# SDISK2_V0_3.net
KiCad netlist of a schematic drawn in EAGLE
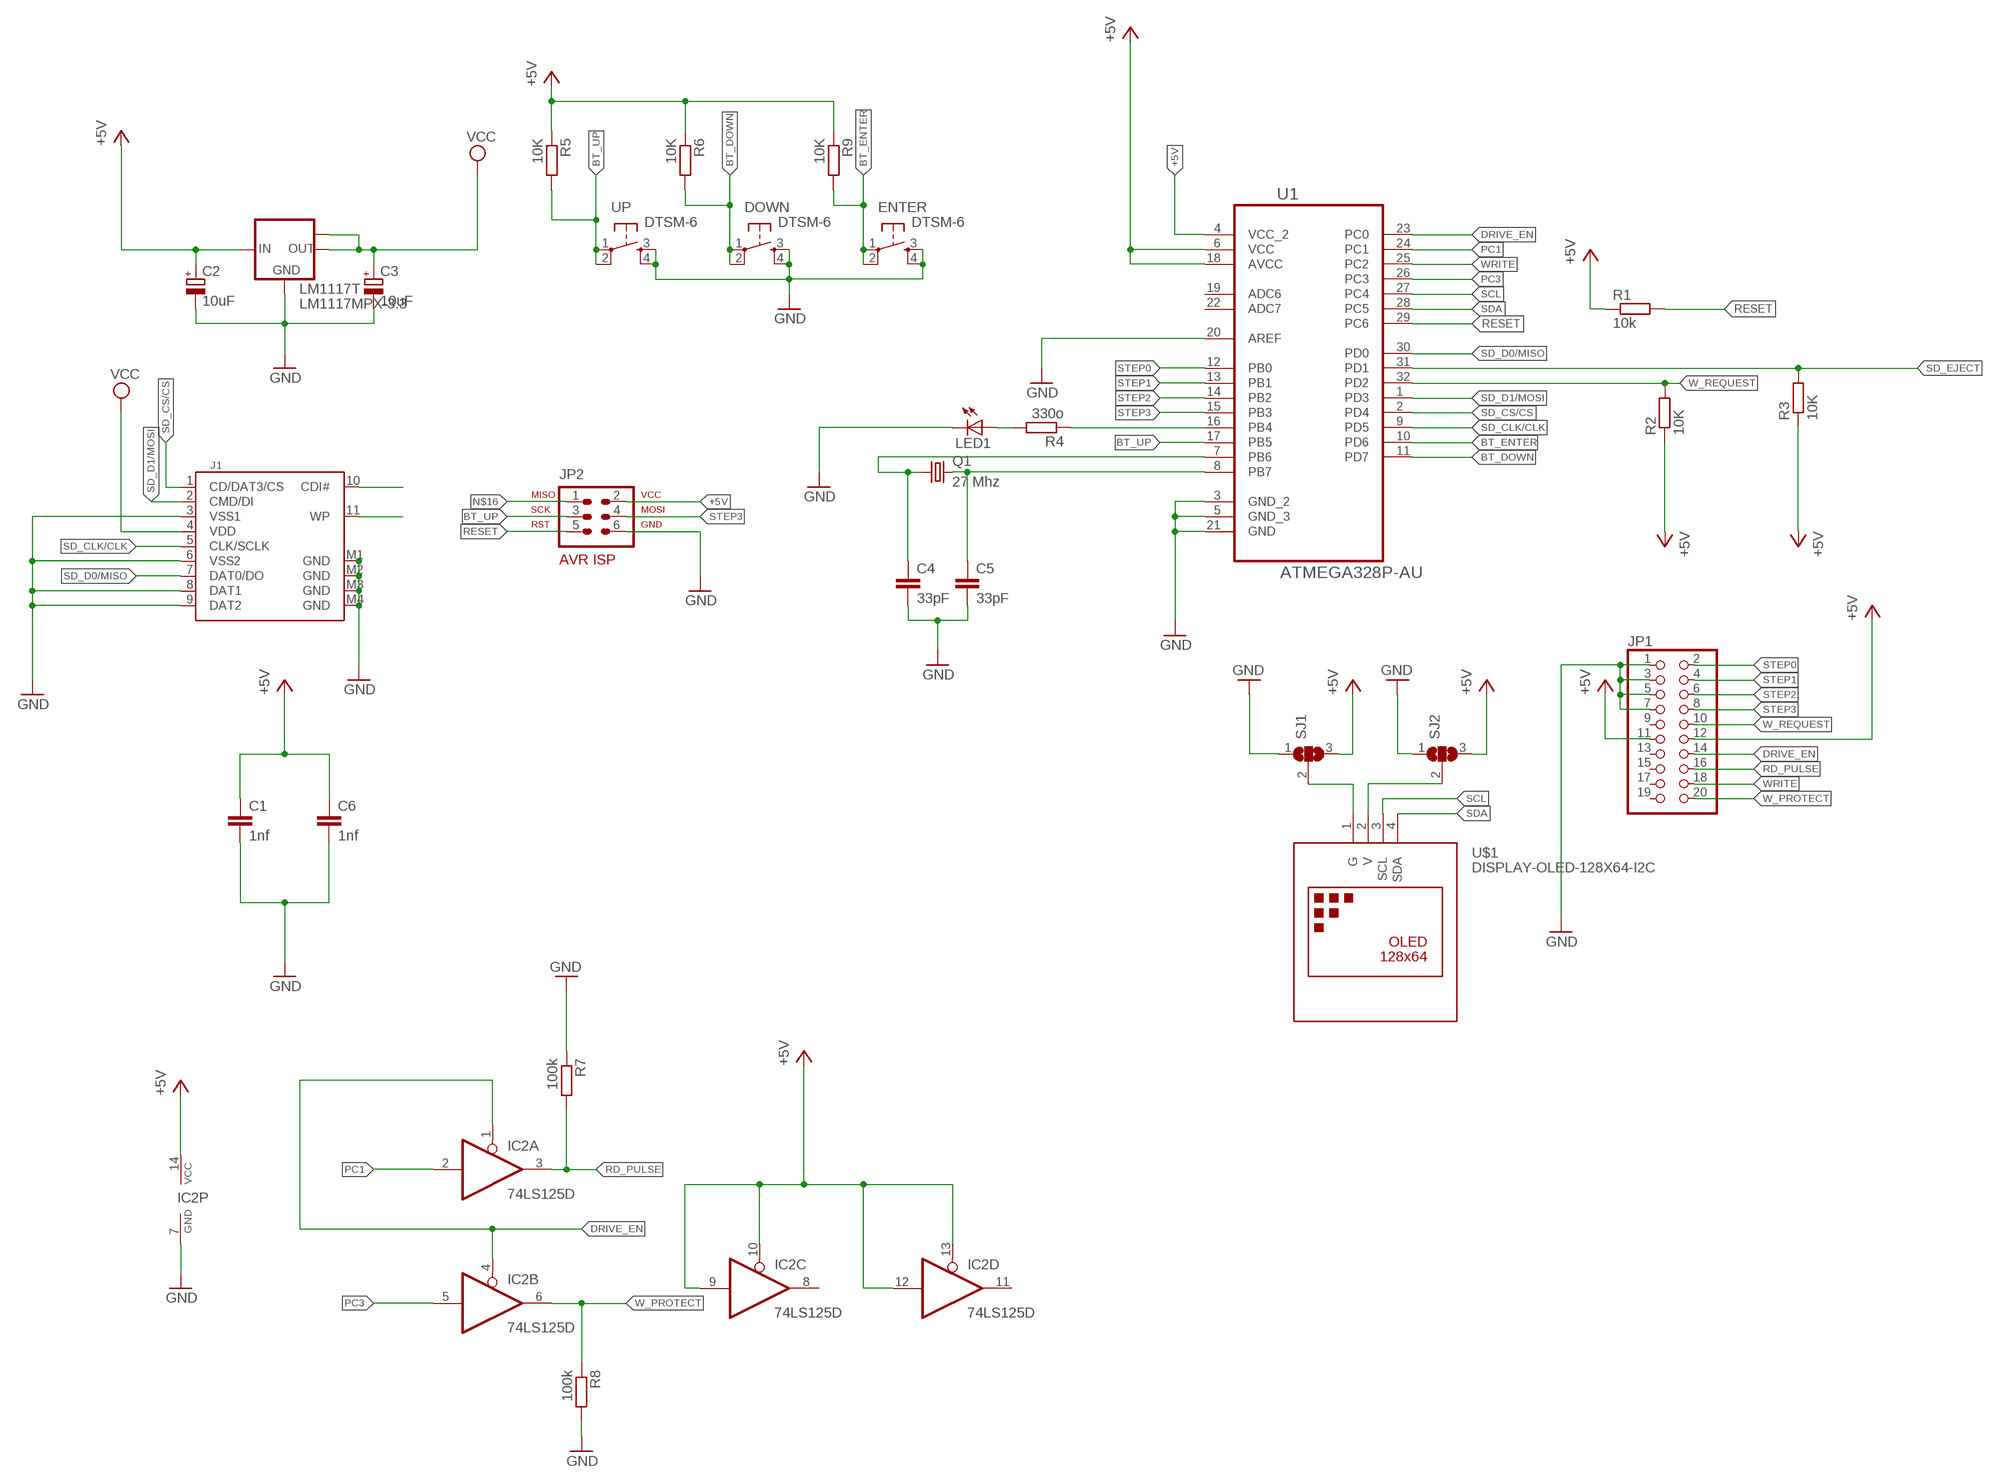
[diagram p0: schematic, sheet 1]

(export (version "E")
  (design (tool "Eeschema 10.0.6"))
  (components
    (comp (ref "C1")
      (value "1nf")
      (footprint "eagle-import:C0805")
      (libsource (lib "eagle-import") (part "C-EUC0805"))
    )
    (comp (ref "C2")
      (value "10uF")
      (footprint "eagle-import:153CLV-0405")
      (libsource (lib "eagle-import") (part "CPOL-EU153CLV-0405"))
    )
    (comp (ref "C3")
      (value "10uF")
      (footprint "eagle-import:153CLV-0405")
      (libsource (lib "eagle-import") (part "CPOL-EU153CLV-0405"))
    )
    (comp (ref "C4")
      (value "33pF")
      (footprint "eagle-import:C0805")
      (libsource (lib "eagle-import") (part "C-EUC0805"))
    )
    (comp (ref "C5")
      (value "33pF")
      (footprint "eagle-import:C0805")
      (libsource (lib "eagle-import") (part "C-EUC0805"))
    )
    (comp (ref "C6")
      (value "1nf")
      (footprint "eagle-import:C0805")
      (libsource (lib "eagle-import") (part "C-EUC0805"))
    )
    (comp (ref "DOWN")
      (value "DTSM-6")
      (footprint "eagle-import:DTSM-6")
      (libsource (lib "eagle-import") (part "DTSM-6"))
    )
    (comp (ref "ENTER")
      (value "DTSM-6")
      (footprint "eagle-import:DTSM-6")
      (libsource (lib "eagle-import") (part "DTSM-6"))
    )
    (comp (ref "IC2")
      (value "74LS125D")
      (footprint "eagle-import:SO14")
      (libsource (lib "eagle-import") (part "74125DLS"))
    )
    (comp (ref "J1")
      (value "SDCARD")
      (footprint "eagle-import:SDCMF-10915W010")
      (libsource (lib "eagle-import") (part "SDCARD"))
    )
    (comp (ref "JP1")
      (value "PINHD-2X10_IDC2X10_IDC_NEW")
      (footprint "eagle-import:2X10_IDC")
      (libsource (lib "eagle-import") (part "PINHD-2X10_IDC2X10_IDC_NEW"))
    )
    (comp (ref "JP2")
      (value "AVR-ISP-6VERT")
      (footprint "eagle-import:AVR-ISP-6")
      (libsource (lib "eagle-import") (part "AVR-ISP-6VERT"))
    )
    (comp (ref "LED1")
      (value "LEDSML1206")
      (footprint "eagle-import:SML1206")
      (libsource (lib "eagle-import") (part "LEDSML1206"))
    )
    (comp (ref "LM1117T")
      (value "LM1117MPX-3.3")
      (footprint "eagle-import:SOT223")
      (libsource (lib "eagle-import") (part "LM1117MPX-3.3"))
    )
    (comp (ref "Q1")
      (value "27 Mhz")
      (footprint "eagle-import:HC49UP")
      (libsource (lib "eagle-import") (part "CRYSTALHC49UP"))
    )
    (comp (ref "R1")
      (value "10k")
      (footprint "eagle-import:R0805")
      (libsource (lib "eagle-import") (part "R-EU_R0805"))
    )
    (comp (ref "R2")
      (value "10K")
      (footprint "eagle-import:R0805")
      (libsource (lib "eagle-import") (part "R-EU_R0805"))
    )
    (comp (ref "R3")
      (value "10K")
      (footprint "eagle-import:R0805")
      (libsource (lib "eagle-import") (part "R-EU_R0805"))
    )
    (comp (ref "R4")
      (value "330o")
      (footprint "eagle-import:R0805")
      (libsource (lib "eagle-import") (part "R-EU_R0805"))
    )
    (comp (ref "R5")
      (value "10K")
      (footprint "eagle-import:R0805")
      (libsource (lib "eagle-import") (part "R-EU_R0805"))
    )
    (comp (ref "R6")
      (value "10K")
      (footprint "eagle-import:R0805")
      (libsource (lib "eagle-import") (part "R-EU_R0805"))
    )
    (comp (ref "R7")
      (value "100k")
      (footprint "eagle-import:R0805")
      (libsource (lib "eagle-import") (part "R-EU_R0805"))
    )
    (comp (ref "R8")
      (value "100k")
      (footprint "eagle-import:R0805")
      (libsource (lib "eagle-import") (part "R-EU_R0805"))
    )
    (comp (ref "R9")
      (value "10K")
      (footprint "eagle-import:R0805")
      (libsource (lib "eagle-import") (part "R-EU_R0805"))
    )
    (comp (ref "SJ1")
      (value "SJ2W")
      (footprint "eagle-import:SJ_2")
      (libsource (lib "eagle-import") (part "SJ2W"))
    )
    (comp (ref "SJ2")
      (value "SJ2W")
      (footprint "eagle-import:SJ_2")
      (libsource (lib "eagle-import") (part "SJ2W"))
    )
    (comp (ref "U$1")
      (value "DISPLAY-OLED-128X64-I2C")
      (footprint "eagle-import:DISPLAY-OLED-128X64-I2C")
      (libsource (lib "eagle-import") (part "DISPLAY-OLED-128X64-I2C"))
    )
    (comp (ref "U1")
      (value "ATMEGA328P-AU")
      (footprint "eagle-import:QFP80P900X900X120-32N")
      (libsource (lib "eagle-import") (part "ATMEGA328P-AU"))
    )
    (comp (ref "UP")
      (value "DTSM-6")
      (footprint "eagle-import:DTSM-6")
      (libsource (lib "eagle-import") (part "DTSM-6"))
    )
  )
  (nets
    (net (code "1") (name "+5V") (class "Default")
      (node (ref "C1") (pin "1") (pinfunction "1_1") (pintype "passive"))
      (node (ref "C2") (pin "+") (pinfunction "+_+") (pintype "passive"))
      (node (ref "C6") (pin "1") (pinfunction "1_1") (pintype "passive"))
      (node (ref "IC2") (pin "10") (pinfunction "OE_10") (pintype "input"))
      (node (ref "IC2") (pin "12") (pinfunction "I_12") (pintype "input"))
      (node (ref "IC2") (pin "13") (pinfunction "OE_13") (pintype "input"))
      (node (ref "IC2") (pin "14") (pinfunction "VCC_14") (pintype "power_in"))
      (node (ref "IC2") (pin "9") (pinfunction "I_9") (pintype "input"))
      (node (ref "JP1") (pin "11") (pinfunction "11_11") (pintype "passive"))
      (node (ref "JP1") (pin "12") (pinfunction "12_12") (pintype "passive"))
      (node (ref "JP2") (pin "2") (pinfunction "2_2") (pintype "passive"))
      (node (ref "LM1117T") (pin "3") (pinfunction "IN_3") (pintype "input"))
      (node (ref "R1") (pin "1") (pinfunction "1_1") (pintype "passive"))
      (node (ref "R2") (pin "1") (pinfunction "1_1") (pintype "passive"))
      (node (ref "R3") (pin "1") (pinfunction "1_1") (pintype "passive"))
      (node (ref "R5") (pin "1") (pinfunction "1_1") (pintype "passive"))
      (node (ref "R6") (pin "1") (pinfunction "1_1") (pintype "passive"))
      (node (ref "R9") (pin "1") (pinfunction "1_1") (pintype "passive"))
      (node (ref "SJ1") (pin "3") (pinfunction "3_3") (pintype "passive"))
      (node (ref "SJ2") (pin "3") (pinfunction "3_3") (pintype "passive"))
      (node (ref "U1") (pin "18") (pinfunction "AVCC_18") (pintype "power_in"))
      (node (ref "U1") (pin "4") (pinfunction "VCC_2_4") (pintype "power_in"))
      (node (ref "U1") (pin "6") (pinfunction "VCC_6") (pintype "power_in"))
    )
    (net (code "2") (name "BT_DOWN") (class "Default")
      (node (ref "DOWN") (pin "1") (pinfunction "1_1") (pintype "passive"))
      (node (ref "DOWN") (pin "2") (pinfunction "2_2") (pintype "passive"))
      (node (ref "R6") (pin "2") (pinfunction "2_2") (pintype "passive"))
      (node (ref "U1") (pin "11") (pinfunction "PD7_11") (pintype "bidirectional"))
    )
    (net (code "3") (name "BT_ENTER") (class "Default")
      (node (ref "ENTER") (pin "1") (pinfunction "1_1") (pintype "passive"))
      (node (ref "ENTER") (pin "2") (pinfunction "2_2") (pintype "passive"))
      (node (ref "R9") (pin "2") (pinfunction "2_2") (pintype "passive"))
      (node (ref "U1") (pin "10") (pinfunction "PD6_10") (pintype "bidirectional"))
    )
    (net (code "4") (name "BT_UP") (class "Default")
      (node (ref "JP2") (pin "3") (pinfunction "3_3") (pintype "passive"))
      (node (ref "R5") (pin "2") (pinfunction "2_2") (pintype "passive"))
      (node (ref "U1") (pin "17") (pinfunction "PB5_17") (pintype "bidirectional"))
      (node (ref "UP") (pin "1") (pinfunction "1_1") (pintype "passive"))
      (node (ref "UP") (pin "2") (pinfunction "2_2") (pintype "passive"))
    )
    (net (code "5") (name "DRIVE_EN") (class "Default")
      (node (ref "IC2") (pin "1") (pinfunction "OE_1") (pintype "input"))
      (node (ref "IC2") (pin "4") (pinfunction "OE_4") (pintype "input"))
      (node (ref "JP1") (pin "14") (pinfunction "14_14") (pintype "passive"))
      (node (ref "U1") (pin "23") (pinfunction "PC0_23") (pintype "bidirectional"))
    )
    (net (code "6") (name "GND") (class "Default")
      (node (ref "C1") (pin "2") (pinfunction "2_2") (pintype "passive"))
      (node (ref "C2") (pin "-") (pinfunction "-_-") (pintype "passive"))
      (node (ref "C3") (pin "-") (pinfunction "-_-") (pintype "passive"))
      (node (ref "C4") (pin "2") (pinfunction "2_2") (pintype "passive"))
      (node (ref "C5") (pin "2") (pinfunction "2_2") (pintype "passive"))
      (node (ref "C6") (pin "2") (pinfunction "2_2") (pintype "passive"))
      (node (ref "DOWN") (pin "3") (pinfunction "3_3") (pintype "passive"))
      (node (ref "DOWN") (pin "4") (pinfunction "4_4") (pintype "passive"))
      (node (ref "ENTER") (pin "3") (pinfunction "3_3") (pintype "passive"))
      (node (ref "ENTER") (pin "4") (pinfunction "4_4") (pintype "passive"))
      (node (ref "IC2") (pin "7") (pinfunction "GND_7") (pintype "power_in"))
      (node (ref "J1") (pin "3") (pinfunction "VSS1_3") (pintype "power_in"))
      (node (ref "J1") (pin "6") (pinfunction "VSS2_6") (pintype "power_in"))
      (node (ref "J1") (pin "8") (pinfunction "DAT1_8") (pintype "bidirectional"))
      (node (ref "J1") (pin "9") (pinfunction "DAT2_9") (pintype "bidirectional"))
      (node (ref "J1") (pin "M1") (pinfunction "GND_M1") (pintype "power_in"))
      (node (ref "J1") (pin "M2") (pinfunction "GND_M2") (pintype "power_in"))
      (node (ref "J1") (pin "M3") (pinfunction "GND_M3") (pintype "power_in"))
      (node (ref "J1") (pin "M4") (pinfunction "GND_M4") (pintype "power_in"))
      (node (ref "JP1") (pin "1") (pinfunction "1_1") (pintype "passive"))
      (node (ref "JP1") (pin "3") (pinfunction "3_3") (pintype "passive"))
      (node (ref "JP1") (pin "5") (pinfunction "5_5") (pintype "passive"))
      (node (ref "JP1") (pin "7") (pinfunction "7_7") (pintype "passive"))
      (node (ref "JP2") (pin "6") (pinfunction "6_6") (pintype "passive"))
      (node (ref "LED1") (pin "C") (pinfunction "C_C") (pintype "passive"))
      (node (ref "LM1117T") (pin "1") (pinfunction "GND_1") (pintype "input"))
      (node (ref "R7") (pin "1") (pinfunction "1_1") (pintype "passive"))
      (node (ref "R8") (pin "2") (pinfunction "2_2") (pintype "passive"))
      (node (ref "SJ1") (pin "1") (pinfunction "1_1") (pintype "passive"))
      (node (ref "SJ2") (pin "1") (pinfunction "1_1") (pintype "passive"))
      (node (ref "U1") (pin "20") (pinfunction "AREF_20") (pintype "input"))
      (node (ref "U1") (pin "21") (pinfunction "GND_21") (pintype "passive"))
      (node (ref "U1") (pin "3") (pinfunction "GND_2_3") (pintype "passive"))
      (node (ref "U1") (pin "5") (pinfunction "GND_3_5") (pintype "passive"))
      (node (ref "UP") (pin "3") (pinfunction "3_3") (pintype "passive"))
      (node (ref "UP") (pin "4") (pinfunction "4_4") (pintype "passive"))
    )
    (net (code "7") (name "N$16") (class "Default")
      (node (ref "JP2") (pin "1") (pinfunction "1_1") (pintype "passive"))
      (node (ref "R4") (pin "1") (pinfunction "1_1") (pintype "passive"))
      (node (ref "U1") (pin "16") (pinfunction "PB4_16") (pintype "bidirectional"))
    )
    (net (code "8") (name "Net-(LED1-PadA)") (class "Default")
      (node (ref "LED1") (pin "A") (pinfunction "A_A") (pintype "passive"))
      (node (ref "R4") (pin "2") (pinfunction "2_2") (pintype "passive"))
    )
    (net (code "9") (name "Net-(U$1-G)") (class "Default")
      (node (ref "SJ1") (pin "2") (pinfunction "2_2") (pintype "passive"))
      (node (ref "U$1") (pin "1") (pinfunction "G_1") (pintype "power_in"))
    )
    (net (code "10") (name "Net-(U$1-V)") (class "Default")
      (node (ref "SJ2") (pin "2") (pinfunction "2_2") (pintype "passive"))
      (node (ref "U$1") (pin "2") (pinfunction "V_2") (pintype "power_in"))
    )
    (net (code "11") (name "Net-(U1-PB6)") (class "Default")
      (node (ref "C4") (pin "1") (pinfunction "1_1") (pintype "passive"))
      (node (ref "Q1") (pin "1") (pinfunction "1_1") (pintype "passive"))
      (node (ref "U1") (pin "7") (pinfunction "PB6_7") (pintype "bidirectional"))
    )
    (net (code "12") (name "Net-(U1-PB7)") (class "Default")
      (node (ref "C5") (pin "1") (pinfunction "1_1") (pintype "passive"))
      (node (ref "Q1") (pin "2") (pinfunction "2_2") (pintype "passive"))
      (node (ref "U1") (pin "8") (pinfunction "PB7_8") (pintype "bidirectional"))
    )
    (net (code "13") (name "PC1") (class "Default")
      (node (ref "IC2") (pin "2") (pinfunction "I_2") (pintype "input"))
      (node (ref "U1") (pin "24") (pinfunction "PC1_24") (pintype "bidirectional"))
    )
    (net (code "14") (name "PC3") (class "Default")
      (node (ref "IC2") (pin "5") (pinfunction "I_5") (pintype "input"))
      (node (ref "U1") (pin "26") (pinfunction "PC3_26") (pintype "bidirectional"))
    )
    (net (code "15") (name "RD_PULSE") (class "Default")
      (node (ref "IC2") (pin "3") (pinfunction "O_3") (pintype "tri_state"))
      (node (ref "JP1") (pin "16") (pinfunction "16_16") (pintype "passive"))
      (node (ref "R7") (pin "2") (pinfunction "2_2") (pintype "passive"))
    )
    (net (code "16") (name "RESET") (class "Default")
      (node (ref "JP2") (pin "5") (pinfunction "5_5") (pintype "passive"))
      (node (ref "R1") (pin "2") (pinfunction "2_2") (pintype "passive"))
      (node (ref "U1") (pin "29") (pinfunction "PC6_29") (pintype "bidirectional"))
    )
    (net (code "17") (name "SCL") (class "Default")
      (node (ref "U$1") (pin "3") (pinfunction "SCL_3") (pintype "bidirectional"))
      (node (ref "U1") (pin "27") (pinfunction "PC4_27") (pintype "bidirectional"))
    )
    (net (code "18") (name "SDA") (class "Default")
      (node (ref "U$1") (pin "4") (pinfunction "SDA_4") (pintype "bidirectional"))
      (node (ref "U1") (pin "28") (pinfunction "PC5_28") (pintype "bidirectional"))
    )
    (net (code "19") (name "SD_CLK{slash}CLK") (class "Default")
      (node (ref "J1") (pin "5") (pinfunction "CLK/SCLK_5") (pintype "bidirectional"))
      (node (ref "U1") (pin "9") (pinfunction "PD5_9") (pintype "bidirectional"))
    )
    (net (code "20") (name "SD_CS{slash}CS") (class "Default")
      (node (ref "J1") (pin "1") (pinfunction "CD/DAT3/CS_1") (pintype "bidirectional"))
      (node (ref "U1") (pin "2") (pinfunction "PD4_2") (pintype "bidirectional"))
    )
    (net (code "21") (name "SD_D0{slash}MISO") (class "Default")
      (node (ref "J1") (pin "7") (pinfunction "DAT0/DO_7") (pintype "bidirectional"))
      (node (ref "U1") (pin "30") (pinfunction "PD0_30") (pintype "bidirectional"))
    )
    (net (code "22") (name "SD_D1{slash}MOSI") (class "Default")
      (node (ref "J1") (pin "2") (pinfunction "CMD/DI_2") (pintype "bidirectional"))
      (node (ref "U1") (pin "1") (pinfunction "PD3_1") (pintype "bidirectional"))
    )
    (net (code "23") (name "SD_EJECT") (class "Default")
      (node (ref "R3") (pin "2") (pinfunction "2_2") (pintype "passive"))
      (node (ref "U1") (pin "31") (pinfunction "PD1_31") (pintype "bidirectional"))
    )
    (net (code "24") (name "STEP0") (class "Default")
      (node (ref "JP1") (pin "2") (pinfunction "2_2") (pintype "passive"))
      (node (ref "U1") (pin "12") (pinfunction "PB0_12") (pintype "bidirectional"))
    )
    (net (code "25") (name "STEP1") (class "Default")
      (node (ref "JP1") (pin "4") (pinfunction "4_4") (pintype "passive"))
      (node (ref "U1") (pin "13") (pinfunction "PB1_13") (pintype "bidirectional"))
    )
    (net (code "26") (name "STEP2") (class "Default")
      (node (ref "JP1") (pin "6") (pinfunction "6_6") (pintype "passive"))
      (node (ref "U1") (pin "14") (pinfunction "PB2_14") (pintype "bidirectional"))
    )
    (net (code "27") (name "STEP3") (class "Default")
      (node (ref "JP1") (pin "8") (pinfunction "8_8") (pintype "passive"))
      (node (ref "JP2") (pin "4") (pinfunction "4_4") (pintype "passive"))
      (node (ref "U1") (pin "15") (pinfunction "PB3_15") (pintype "bidirectional"))
    )
    (net (code "28") (name "VCC") (class "Default")
      (node (ref "C3") (pin "+") (pinfunction "+_+") (pintype "passive"))
      (node (ref "J1") (pin "4") (pinfunction "VDD_4") (pintype "power_in"))
      (node (ref "LM1117T") (pin "2") (pinfunction "OUT_2") (pintype "passive"))
      (node (ref "LM1117T") (pin "TAB") (pinfunction "OUT1_TAB") (pintype "passive"))
    )
    (net (code "29") (name "WRITE") (class "Default")
      (node (ref "JP1") (pin "18") (pinfunction "18_18") (pintype "passive"))
      (node (ref "U1") (pin "25") (pinfunction "PC2_25") (pintype "bidirectional"))
    )
    (net (code "30") (name "W_PROTECT") (class "Default")
      (node (ref "IC2") (pin "6") (pinfunction "O_6") (pintype "tri_state"))
      (node (ref "JP1") (pin "20") (pinfunction "20_20") (pintype "passive"))
      (node (ref "R8") (pin "1") (pinfunction "1_1") (pintype "passive"))
    )
    (net (code "31") (name "W_REQUEST") (class "Default")
      (node (ref "JP1") (pin "10") (pinfunction "10_10") (pintype "passive"))
      (node (ref "R2") (pin "2") (pinfunction "2_2") (pintype "passive"))
      (node (ref "U1") (pin "32") (pinfunction "PD2_32") (pintype "bidirectional"))
    )
    (net (code "32") (name "unconnected-(IC2C-O-Pad8)") (class "Default")
      (node (ref "IC2") (pin "8") (pinfunction "O_8") (pintype "tri_state"))
    )
    (net (code "33") (name "unconnected-(IC2D-O-Pad11)") (class "Default")
      (node (ref "IC2") (pin "11") (pinfunction "O_11") (pintype "tri_state"))
    )
    (net (code "34") (name "unconnected-(J1-CDI#-Pad10)") (class "Default")
      (node (ref "J1") (pin "10") (pinfunction "CDI#_10") (pintype "output"))
    )
    (net (code "35") (name "unconnected-(J1-WP-Pad11)") (class "Default")
      (node (ref "J1") (pin "11") (pinfunction "WP_11") (pintype "output"))
    )
    (net (code "36") (name "unconnected-(JP1-Pad9)") (class "Default")
      (node (ref "JP1") (pin "9") (pinfunction "9_9") (pintype "passive"))
    )
    (net (code "37") (name "unconnected-(JP1-Pad13)") (class "Default")
      (node (ref "JP1") (pin "13") (pinfunction "13_13") (pintype "passive"))
    )
    (net (code "38") (name "unconnected-(JP1-Pad15)") (class "Default")
      (node (ref "JP1") (pin "15") (pinfunction "15_15") (pintype "passive"))
    )
    (net (code "39") (name "unconnected-(JP1-Pad17)") (class "Default")
      (node (ref "JP1") (pin "17") (pinfunction "17_17") (pintype "passive"))
    )
    (net (code "40") (name "unconnected-(JP1-Pad19)") (class "Default")
      (node (ref "JP1") (pin "19") (pinfunction "19_19") (pintype "passive"))
    )
    (net (code "41") (name "unconnected-(U1-ADC6-Pad19)") (class "Default")
      (node (ref "U1") (pin "19") (pinfunction "ADC6_19") (pintype "input"))
    )
    (net (code "42") (name "unconnected-(U1-ADC7-Pad22)") (class "Default")
      (node (ref "U1") (pin "22") (pinfunction "ADC7_22") (pintype "input"))
    )
  )
)
